# ChongTromSim808.net
KiCad netlist of a schematic drawn in Altium Designer
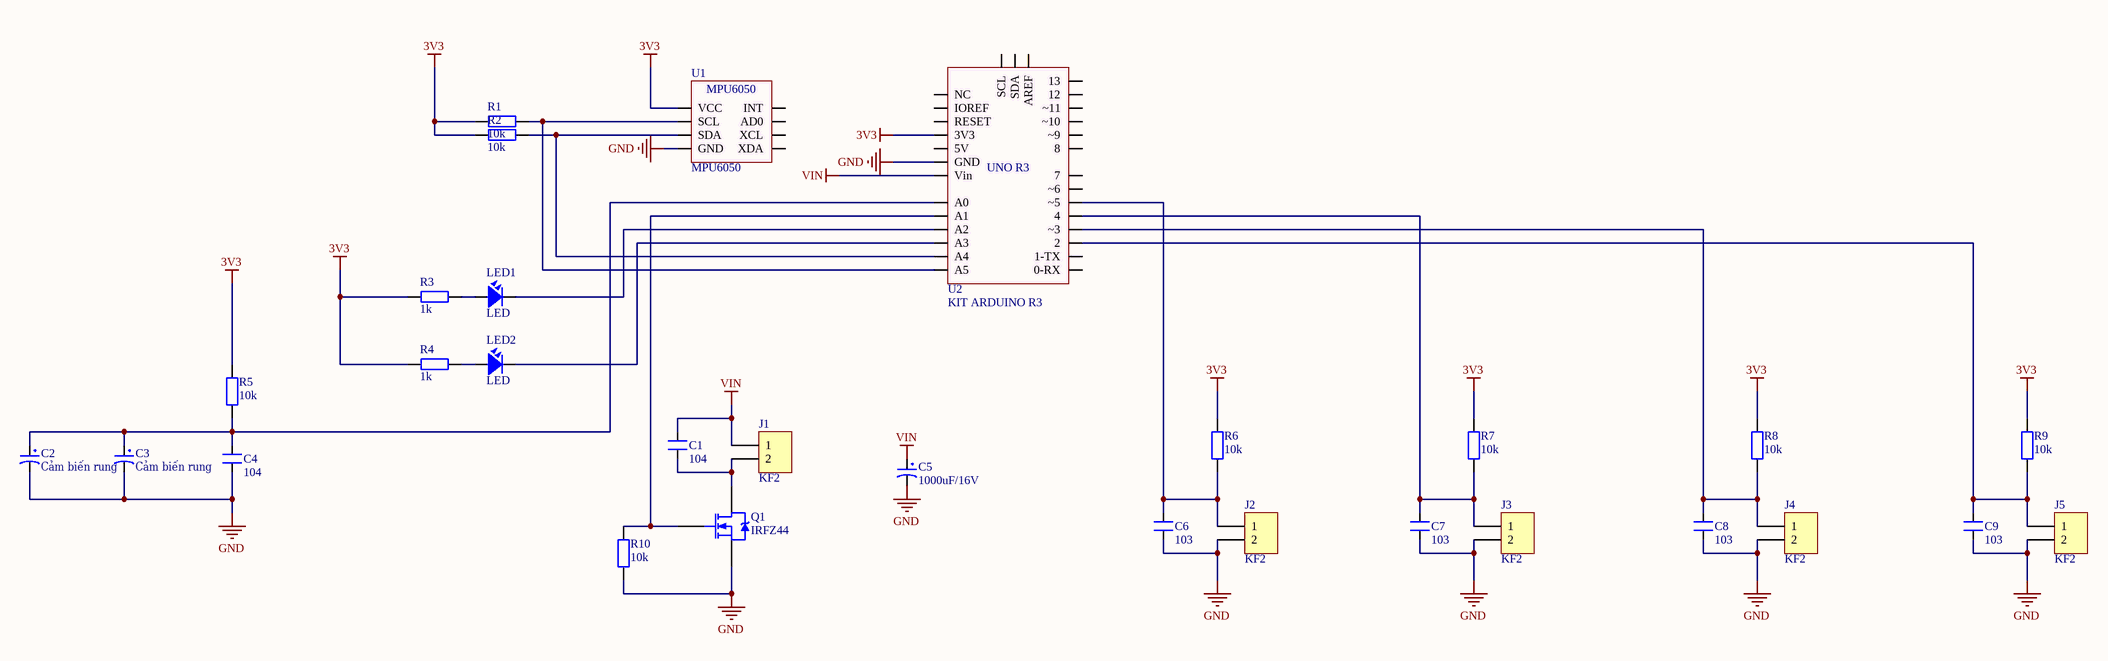
[diagram p0: ChongTromSim808.SchDoc]

(export (version "E")
  (design (tool "Eeschema 10.0.6"))
  (components
    (comp (ref "C1")
      (value "104")
      (footprint "CN2")
      (description "Cap np 104 => 105pF")
      (libsource (lib "OBIT_TESLA") (part "CN2"))
    )
    (comp (ref "C2")
      (value "Cảm biến rung")
      (footprint "CP1.5/3.4")
      (description "Cap 100uF/35V - 470uF/16V")
      (libsource (lib "OBIT_TESLA") (part "CP3"))
    )
    (comp (ref "C3")
      (value "Cảm biến rung")
      (footprint "CP1.5/3.4")
      (description "Cap 100uF/35V - 470uF/16V")
      (libsource (lib "OBIT_TESLA") (part "CP3"))
    )
    (comp (ref "C4")
      (value "104")
      (footprint "CN2")
      (description "Cap np 104 => 105pF")
      (libsource (lib "OBIT_TESLA") (part "CN2"))
    )
    (comp (ref "C5")
      (value "1000uF/16V")
      (footprint "CP1.5/3.4")
      (description "Cap 1000uF/16V - 220uF/50V")
      (libsource (lib "OBIT_TESLA") (part "CP4"))
    )
    (comp (ref "C6")
      (value "103")
      (footprint "SM-0805")
      (description "Cap SMD")
      (libsource (lib "OBIT_TESLA") (part "CM"))
    )
    (comp (ref "C7")
      (value "103")
      (footprint "SM-0805")
      (description "Cap SMD")
      (libsource (lib "OBIT_TESLA") (part "CM"))
    )
    (comp (ref "C8")
      (value "103")
      (footprint "SM-0805")
      (description "Cap SMD")
      (libsource (lib "OBIT_TESLA") (part "CM"))
    )
    (comp (ref "C9")
      (value "103")
      (footprint "SM-0805")
      (description "Cap SMD")
      (libsource (lib "OBIT_TESLA") (part "CM"))
    )
    (comp (ref "J1")
      (value "KF2")
      (footprint "KF2-3.5")
      (fields
        (field (name "MANUFACTURER") "Würth Elektronik eiSos GmbH")
        (field (name "PARTNO") "691103110002")
        (field (name "CREATED BY") "Karrer Zheng")
      )
      (libsource (lib "OBIT_TESLA") (part "KF2"))
    )
    (comp (ref "J2")
      (value "KF2")
      (footprint "KF2-3.5")
      (fields
        (field (name "MANUFACTURER") "Würth Elektronik eiSos GmbH")
        (field (name "PARTNO") "691103110002")
        (field (name "CREATED BY") "Karrer Zheng")
      )
      (libsource (lib "OBIT_TESLA") (part "KF2"))
    )
    (comp (ref "J3")
      (value "KF2")
      (footprint "KF2-3.5")
      (fields
        (field (name "MANUFACTURER") "Würth Elektronik eiSos GmbH")
        (field (name "PARTNO") "691103110002")
        (field (name "CREATED BY") "Karrer Zheng")
      )
      (libsource (lib "OBIT_TESLA") (part "KF2"))
    )
    (comp (ref "J4")
      (value "KF2")
      (footprint "KF2-3.5")
      (fields
        (field (name "MANUFACTURER") "Würth Elektronik eiSos GmbH")
        (field (name "PARTNO") "691103110002")
        (field (name "CREATED BY") "Karrer Zheng")
      )
      (libsource (lib "OBIT_TESLA") (part "KF2"))
    )
    (comp (ref "J5")
      (value "KF2")
      (footprint "KF2-3.5")
      (fields
        (field (name "MANUFACTURER") "Würth Elektronik eiSos GmbH")
        (field (name "PARTNO") "691103110002")
        (field (name "CREATED BY") "Karrer Zheng")
      )
      (libsource (lib "OBIT_TESLA") (part "KF2"))
    )
    (comp (ref "LED1") (value "LED") (footprint "LED-5-WHITE") (libsource (lib "OBIT_TESLA") (part "LED")))
    (comp (ref "LED2") (value "LED") (footprint "LED-5-BLUE") (libsource (lib "OBIT_TESLA") (part "LED")))
    (comp (ref "Q1") (value "IRFZ44") (footprint "TO220-123") (libsource (lib "OBIT_TESLA") (part "IRFZ44")))
    (comp (ref "R1")
      (value "10k")
      (footprint "RES-1/4W")
      (description "Resistor R1/4W")
      (libsource (lib "OBIT_TESLA") (part "R"))
    )
    (comp (ref "R2")
      (value "10k")
      (footprint "RES-1/4W")
      (description "Resistor R1/4W")
      (libsource (lib "OBIT_TESLA") (part "R"))
    )
    (comp (ref "R3")
      (value "1k")
      (footprint "RES-1/4W")
      (description "Resistor R1/4W")
      (libsource (lib "OBIT_TESLA") (part "R"))
    )
    (comp (ref "R4")
      (value "1k")
      (footprint "RES-1/4W")
      (description "Resistor R1/4W")
      (libsource (lib "OBIT_TESLA") (part "R"))
    )
    (comp (ref "R5")
      (value "10k")
      (footprint "RES-1/4W")
      (description "Resistor R1/4W")
      (libsource (lib "OBIT_TESLA") (part "R"))
    )
    (comp (ref "R6")
      (value "10k")
      (footprint "RES-1/4W")
      (description "Resistor R1/4W")
      (libsource (lib "OBIT_TESLA") (part "R"))
    )
    (comp (ref "R7")
      (value "10k")
      (footprint "RES-1/4W")
      (description "Resistor R1/4W")
      (libsource (lib "OBIT_TESLA") (part "R"))
    )
    (comp (ref "R8")
      (value "10k")
      (footprint "RES-1/4W")
      (description "Resistor R1/4W")
      (libsource (lib "OBIT_TESLA") (part "R"))
    )
    (comp (ref "R9")
      (value "10k")
      (footprint "RES-1/4W")
      (description "Resistor R1/4W")
      (libsource (lib "OBIT_TESLA") (part "R"))
    )
    (comp (ref "R10")
      (value "10k")
      (footprint "RES-1/4W")
      (description "Resistor R1/4W")
      (libsource (lib "OBIT_TESLA") (part "R"))
    )
    (comp (ref "U1") (value "MPU6050") (footprint "MPU6050") (libsource (lib "MCU") (part "MPU6050")))
    (comp (ref "U2")
      (value "KIT ARDUINO R3")
      (footprint "Arduino UNO R3 - v1")
      (description "ARDUINO  R3 ATMEGA328, ARDUINO UNO, EVAL BOARD")
      (libsource (lib "MCU") (part "KIT ARDUINO R3"))
    )
  )
  (nets
    (net (code "1") (name "3V3") (class "Default")
      (node (ref "R1") (pin "1") (pinfunction "1_1") (pintype "passive"))
      (node (ref "R2") (pin "1") (pinfunction "1_1") (pintype "passive"))
      (node (ref "R3") (pin "1") (pinfunction "1_1") (pintype "passive"))
      (node (ref "R4") (pin "1") (pinfunction "1_1") (pintype "passive"))
      (node (ref "R5") (pin "2") (pinfunction "2_2") (pintype "passive"))
      (node (ref "R6") (pin "2") (pinfunction "2_2") (pintype "passive"))
      (node (ref "R7") (pin "2") (pinfunction "2_2") (pintype "passive"))
      (node (ref "R8") (pin "2") (pinfunction "2_2") (pintype "passive"))
      (node (ref "R9") (pin "2") (pinfunction "2_2") (pintype "passive"))
      (node (ref "U1") (pin "1") (pinfunction "VCC_1") (pintype "passive"))
      (node (ref "U2") (pin "3V3") (pinfunction "3V3_3V3") (pintype "passive"))
    )
    (net (code "2") (name "GND") (class "Default")
      (node (ref "C2") (pin "2") (pinfunction "2_2") (pintype "passive"))
      (node (ref "C3") (pin "2") (pinfunction "2_2") (pintype "passive"))
      (node (ref "C4") (pin "1") (pinfunction "1_1") (pintype "passive"))
      (node (ref "C5") (pin "2") (pinfunction "2_2") (pintype "passive"))
      (node (ref "C6") (pin "1") (pinfunction "1_1") (pintype "passive"))
      (node (ref "C7") (pin "1") (pinfunction "1_1") (pintype "passive"))
      (node (ref "C8") (pin "1") (pinfunction "1_1") (pintype "passive"))
      (node (ref "C9") (pin "1") (pinfunction "1_1") (pintype "passive"))
      (node (ref "J2") (pin "2") (pinfunction "2_2") (pintype "passive"))
      (node (ref "J3") (pin "2") (pinfunction "2_2") (pintype "passive"))
      (node (ref "J4") (pin "2") (pinfunction "2_2") (pintype "passive"))
      (node (ref "J5") (pin "2") (pinfunction "2_2") (pintype "passive"))
      (node (ref "Q1") (pin "3") (pinfunction "S_3") (pintype "passive"))
      (node (ref "R10") (pin "1") (pinfunction "1_1") (pintype "passive"))
      (node (ref "U1") (pin "2") (pinfunction "GND_2") (pintype "passive"))
      (node (ref "U2") (pin "GND") (pinfunction "GND_GND") (pintype "passive"))
    )
    (net (code "3") (name "Net-(C2-Pad1)") (class "Default")
      (node (ref "C2") (pin "1") (pinfunction "1_1") (pintype "passive"))
      (node (ref "C3") (pin "1") (pinfunction "1_1") (pintype "passive"))
      (node (ref "C4") (pin "2") (pinfunction "2_2") (pintype "passive"))
      (node (ref "R5") (pin "1") (pinfunction "1_1") (pintype "passive"))
      (node (ref "U2") (pin "A0") (pinfunction "A0_A0") (pintype "passive"))
    )
    (net (code "4") (name "Net-(C6-Pad2)") (class "Default")
      (node (ref "C6") (pin "2") (pinfunction "2_2") (pintype "passive"))
      (node (ref "J2") (pin "1") (pinfunction "1_1") (pintype "passive"))
      (node (ref "R6") (pin "1") (pinfunction "1_1") (pintype "passive"))
      (node (ref "U2") (pin "~5") (pinfunction "~5_~5") (pintype "passive"))
    )
    (net (code "5") (name "Net-(C7-Pad2)") (class "Default")
      (node (ref "C7") (pin "2") (pinfunction "2_2") (pintype "passive"))
      (node (ref "J3") (pin "1") (pinfunction "1_1") (pintype "passive"))
      (node (ref "R7") (pin "1") (pinfunction "1_1") (pintype "passive"))
      (node (ref "U2") (pin "4") (pinfunction "4_4") (pintype "passive"))
    )
    (net (code "6") (name "Net-(C8-Pad2)") (class "Default")
      (node (ref "C8") (pin "2") (pinfunction "2_2") (pintype "passive"))
      (node (ref "J4") (pin "1") (pinfunction "1_1") (pintype "passive"))
      (node (ref "R8") (pin "1") (pinfunction "1_1") (pintype "passive"))
      (node (ref "U2") (pin "~3") (pinfunction "~3_~3") (pintype "passive"))
    )
    (net (code "7") (name "Net-(C9-Pad2)") (class "Default")
      (node (ref "C9") (pin "2") (pinfunction "2_2") (pintype "passive"))
      (node (ref "J5") (pin "1") (pinfunction "1_1") (pintype "passive"))
      (node (ref "R9") (pin "1") (pinfunction "1_1") (pintype "passive"))
      (node (ref "U2") (pin "2") (pinfunction "2_2") (pintype "passive"))
    )
    (net (code "8") (name "Net-(LED1-Pad1)") (class "Default")
      (node (ref "LED1") (pin "1") (pinfunction "1_1") (pintype "passive"))
      (node (ref "R3") (pin "2") (pinfunction "2_2") (pintype "passive"))
    )
    (net (code "9") (name "Net-(LED1-Pad2)") (class "Default")
      (node (ref "LED1") (pin "2") (pinfunction "2_2") (pintype "passive"))
      (node (ref "U2") (pin "A2") (pinfunction "A2_A2") (pintype "passive"))
    )
    (net (code "10") (name "Net-(LED2-Pad1)") (class "Default")
      (node (ref "LED2") (pin "1") (pinfunction "1_1") (pintype "passive"))
      (node (ref "R4") (pin "2") (pinfunction "2_2") (pintype "passive"))
    )
    (net (code "11") (name "Net-(LED2-Pad2)") (class "Default")
      (node (ref "LED2") (pin "2") (pinfunction "2_2") (pintype "passive"))
      (node (ref "U2") (pin "A3") (pinfunction "A3_A3") (pintype "passive"))
    )
    (net (code "12") (name "Net-(Q1-D)") (class "Default")
      (node (ref "C1") (pin "1") (pinfunction "1_1") (pintype "passive"))
      (node (ref "J1") (pin "2") (pinfunction "2_2") (pintype "passive"))
      (node (ref "Q1") (pin "2") (pinfunction "D_2") (pintype "passive"))
    )
    (net (code "13") (name "Net-(Q1-G)") (class "Default")
      (node (ref "Q1") (pin "1") (pinfunction "G_1") (pintype "passive"))
      (node (ref "R10") (pin "2") (pinfunction "2_2") (pintype "passive"))
      (node (ref "U2") (pin "A1") (pinfunction "A1_A1") (pintype "passive"))
    )
    (net (code "14") (name "Net-(U1-SCL)") (class "Default")
      (node (ref "R1") (pin "2") (pinfunction "2_2") (pintype "passive"))
      (node (ref "U1") (pin "3") (pinfunction "SCL_3") (pintype "passive"))
      (node (ref "U2") (pin "A5") (pinfunction "A5_A5") (pintype "passive"))
    )
    (net (code "15") (name "Net-(U1-SDA)") (class "Default")
      (node (ref "R2") (pin "2") (pinfunction "2_2") (pintype "passive"))
      (node (ref "U1") (pin "4") (pinfunction "SDA_4") (pintype "passive"))
      (node (ref "U2") (pin "A4") (pinfunction "A4_A4") (pintype "passive"))
    )
    (net (code "16") (name "VIN") (class "Default")
      (node (ref "C1") (pin "2") (pinfunction "2_2") (pintype "passive"))
      (node (ref "C5") (pin "1") (pinfunction "1_1") (pintype "passive"))
      (node (ref "J1") (pin "1") (pinfunction "1_1") (pintype "passive"))
      (node (ref "U2") (pin "Vin") (pinfunction "Vin_Vin") (pintype "passive"))
    )
    (net (code "17") (name "unconnected-(U1-AD0-Pad7)") (class "Default")
      (node (ref "U1") (pin "7") (pinfunction "AD0_7") (pintype "passive"))
    )
    (net (code "18") (name "unconnected-(U1-INT-Pad8)") (class "Default")
      (node (ref "U1") (pin "8") (pinfunction "INT_8") (pintype "passive"))
    )
    (net (code "19") (name "unconnected-(U1-XCL-Pad6)") (class "Default")
      (node (ref "U1") (pin "6") (pinfunction "XCL_6") (pintype "passive"))
    )
    (net (code "20") (name "unconnected-(U1-XDA-Pad5)") (class "Default")
      (node (ref "U1") (pin "5") (pinfunction "XDA_5") (pintype "passive"))
    )
    (net (code "21") (name "unconnected-(U2-Pad0-RX)") (class "Default")
      (node (ref "U2") (pin "0-RX") (pinfunction "0-RX_0-RX") (pintype "passive"))
    )
    (net (code "22") (name "unconnected-(U2-Pad1-TX)") (class "Default")
      (node (ref "U2") (pin "1-TX") (pinfunction "1-TX_1-TX") (pintype "passive"))
    )
    (net (code "23") (name "unconnected-(U2-Pad5V)") (class "Default")
      (node (ref "U2") (pin "5V") (pinfunction "5V_5V") (pintype "passive"))
    )
    (net (code "24") (name "unconnected-(U2-Pad7)") (class "Default")
      (node (ref "U2") (pin "7") (pinfunction "7_7") (pintype "passive"))
    )
    (net (code "25") (name "unconnected-(U2-Pad8)") (class "Default")
      (node (ref "U2") (pin "8") (pinfunction "8_8") (pintype "passive"))
    )
    (net (code "26") (name "unconnected-(U2-Pad12)") (class "Default")
      (node (ref "U2") (pin "12") (pinfunction "12_12") (pintype "passive"))
    )
    (net (code "27") (name "unconnected-(U2-Pad13)") (class "Default")
      (node (ref "U2") (pin "13") (pinfunction "13_13") (pintype "passive"))
    )
    (net (code "28") (name "unconnected-(U2-PadAREF)") (class "Default")
      (node (ref "U2") (pin "AREF") (pinfunction "AREF_AREF") (pintype "passive"))
    )
    (net (code "29") (name "unconnected-(U2-PadIOREF)") (class "Default")
      (node (ref "U2") (pin "IOREF") (pinfunction "IOREF_IOREF") (pintype "passive"))
    )
    (net (code "30") (name "unconnected-(U2-PadNC)") (class "Default")
      (node (ref "U2") (pin "NC") (pinfunction "NC_NC") (pintype "passive"))
    )
    (net (code "31") (name "unconnected-(U2-PadRESET)") (class "Default")
      (node (ref "U2") (pin "RESET") (pinfunction "RESET_RESET") (pintype "passive"))
    )
    (net (code "32") (name "unconnected-(U2-PadSCL)") (class "Default")
      (node (ref "U2") (pin "SCL") (pinfunction "SCL_SCL") (pintype "passive"))
    )
    (net (code "33") (name "unconnected-(U2-PadSDA)") (class "Default")
      (node (ref "U2") (pin "SDA") (pinfunction "SDA_SDA") (pintype "passive"))
    )
    (net (code "34") (name "unconnected-(U2-Pad~6)") (class "Default")
      (node (ref "U2") (pin "~6") (pinfunction "~6_~6") (pintype "passive"))
    )
    (net (code "35") (name "unconnected-(U2-Pad~9)") (class "Default")
      (node (ref "U2") (pin "~9") (pinfunction "~9_~9") (pintype "passive"))
    )
    (net (code "36") (name "unconnected-(U2-Pad~10)") (class "Default")
      (node (ref "U2") (pin "~10") (pinfunction "~10_~10") (pintype "passive"))
    )
    (net (code "37") (name "unconnected-(U2-Pad~11)") (class "Default")
      (node (ref "U2") (pin "~11") (pinfunction "~11_~11") (pintype "passive"))
    )
  )
)
